# Motor1.net
KiCad netlist of a schematic drawn in Altium Designer
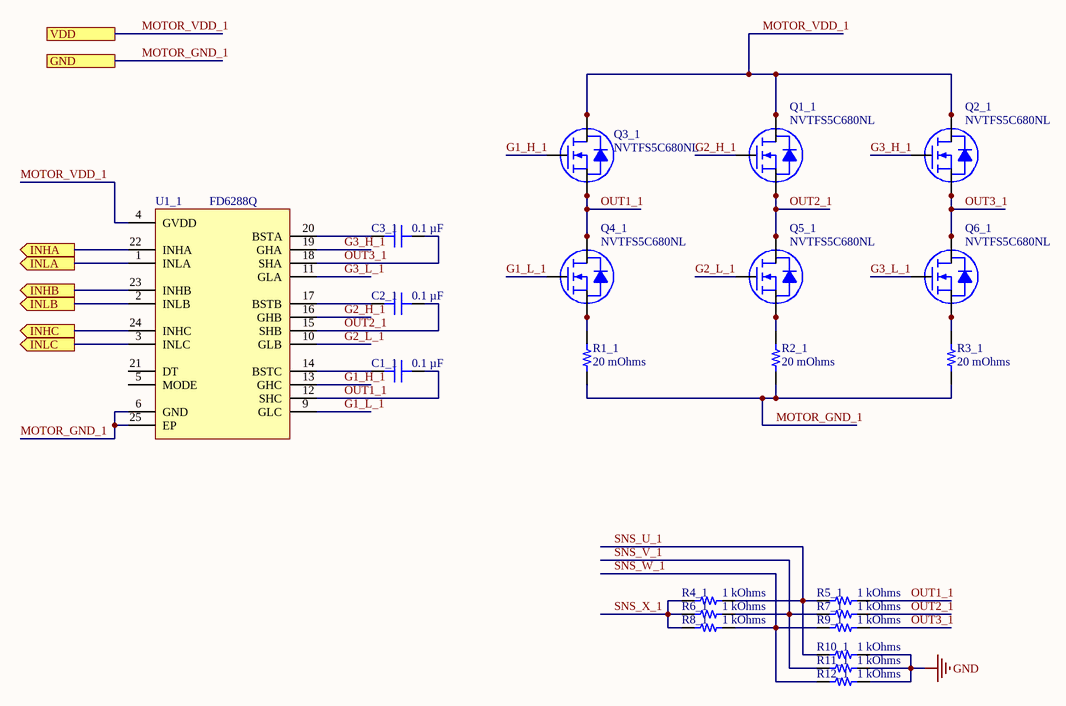
[diagram p0: Motor1.SchDoc]

(export (version "E")
  (design (tool "Eeschema 10.0.6"))
  (components
    (comp (ref "C1_1")
      (value "0.1 µF")
      (footprint "CAP 0402_1005")
      (description "CAP CER 0.1UF 16V X7R 0402")
      (fields (field (name "PART NUMBER") "C0402C104K4RACAUTO") (field (name "MANUFACTURER") "KEMET"))
      (libsource (lib "Celestial Altium Library - altium_library") (part "Capacitor"))
    )
    (comp (ref "C2_1")
      (value "0.1 µF")
      (footprint "CAP 0402_1005")
      (description "CAP CER 0.1UF 16V X7R 0402")
      (fields (field (name "PART NUMBER") "C0402C104K4RACAUTO") (field (name "MANUFACTURER") "KEMET"))
      (libsource (lib "Celestial Altium Library - altium_library") (part "Capacitor"))
    )
    (comp (ref "C3_1")
      (value "0.1 µF")
      (footprint "CAP 0402_1005")
      (description "CAP CER 0.1UF 16V X7R 0402")
      (fields (field (name "PART NUMBER") "C0402C104K4RACAUTO") (field (name "MANUFACTURER") "KEMET"))
      (libsource (lib "Celestial Altium Library - altium_library") (part "Capacitor"))
    )
    (comp (ref "Q1_1")
      (value "NVTFS5C680NL")
      (footprint "NVTFS015N04CTAG")
      (description "N-FET")
      (libsource (lib "IC") (part "NVTFS5C680NL"))
    )
    (comp (ref "Q2_1")
      (value "NVTFS5C680NL")
      (footprint "NVTFS015N04CTAG")
      (description "N-FET")
      (libsource (lib "IC") (part "NVTFS5C680NL"))
    )
    (comp (ref "Q3_1")
      (value "NVTFS5C680NL")
      (footprint "NVTFS015N04CTAG")
      (description "N-FET")
      (libsource (lib "IC") (part "NVTFS5C680NL"))
    )
    (comp (ref "Q4_1")
      (value "NVTFS5C680NL")
      (footprint "NVTFS015N04CTAG")
      (description "N-FET")
      (libsource (lib "IC") (part "NVTFS5C680NL"))
    )
    (comp (ref "Q5_1")
      (value "NVTFS5C680NL")
      (footprint "NVTFS015N04CTAG")
      (description "N-FET")
      (libsource (lib "IC") (part "NVTFS5C680NL"))
    )
    (comp (ref "Q6_1")
      (value "NVTFS5C680NL")
      (footprint "NVTFS015N04CTAG")
      (description "N-FET")
      (libsource (lib "IC") (part "NVTFS5C680NL"))
    )
    (comp (ref "R1_1")
      (value "20 mOhms")
      (footprint "STACKPOLE CSR0805")
      (description "RES 0.02 OHM 1% 1/3W 0603")
      (fields
        (field (name "PART NUMBER") "ERJ-3BWFR020V")
        (field (name "MANUFACTURER") "Panasonic Electronic Components")
      )
      (libsource (lib "Celestial Altium Library - altium_library") (part "Resistor"))
    )
    (comp (ref "R2_1")
      (value "20 mOhms")
      (footprint "STACKPOLE CSR0805")
      (description "RES 0.02 OHM 1% 1/3W 0603")
      (fields
        (field (name "PART NUMBER") "ERJ-3BWFR020V")
        (field (name "MANUFACTURER") "Panasonic Electronic Components")
      )
      (libsource (lib "Celestial Altium Library - altium_library") (part "Resistor"))
    )
    (comp (ref "R3_1")
      (value "20 mOhms")
      (footprint "STACKPOLE CSR0805")
      (description "RES 0.02 OHM 1% 1/3W 0603")
      (fields
        (field (name "PART NUMBER") "ERJ-3BWFR020V")
        (field (name "MANUFACTURER") "Panasonic Electronic Components")
      )
      (libsource (lib "Celestial Altium Library - altium_library") (part "Resistor"))
    )
    (comp (ref "R4_1")
      (value "1 kOhms")
      (footprint "RES 0402_1005")
      (description "RES 14.3K OHM 1% 1/10W 0402")
      (fields
        (field (name "PART NUMBER") "RK73H1ETTP1432F")
        (field (name "MANUFACTURER") "KOA Speer Electronics, Inc.")
      )
      (libsource (lib "Celestial Altium Library - altium_library") (part "Resistor"))
    )
    (comp (ref "R5_1")
      (value "1 kOhms")
      (footprint "RES 0402_1005")
      (description "RES 14.3K OHM 1% 1/10W 0402")
      (fields
        (field (name "PART NUMBER") "RK73H1ETTP1432F")
        (field (name "MANUFACTURER") "KOA Speer Electronics, Inc.")
      )
      (libsource (lib "Celestial Altium Library - altium_library") (part "Resistor"))
    )
    (comp (ref "R6_1")
      (value "1 kOhms")
      (footprint "RES 0402_1005")
      (description "RES 14.3K OHM 1% 1/10W 0402")
      (fields
        (field (name "PART NUMBER") "RK73H1ETTP1432F")
        (field (name "MANUFACTURER") "KOA Speer Electronics, Inc.")
      )
      (libsource (lib "Celestial Altium Library - altium_library") (part "Resistor"))
    )
    (comp (ref "R7_1")
      (value "1 kOhms")
      (footprint "RES 0402_1005")
      (description "RES 14.3K OHM 1% 1/10W 0402")
      (fields
        (field (name "PART NUMBER") "RK73H1ETTP1432F")
        (field (name "MANUFACTURER") "KOA Speer Electronics, Inc.")
      )
      (libsource (lib "Celestial Altium Library - altium_library") (part "Resistor"))
    )
    (comp (ref "R8_1")
      (value "1 kOhms")
      (footprint "RES 0402_1005")
      (description "RES 14.3K OHM 1% 1/10W 0402")
      (fields
        (field (name "PART NUMBER") "RK73H1ETTP1432F")
        (field (name "MANUFACTURER") "KOA Speer Electronics, Inc.")
      )
      (libsource (lib "Celestial Altium Library - altium_library") (part "Resistor"))
    )
    (comp (ref "R9_1")
      (value "1 kOhms")
      (footprint "RES 0402_1005")
      (description "RES 14.3K OHM 1% 1/10W 0402")
      (fields
        (field (name "PART NUMBER") "RK73H1ETTP1432F")
        (field (name "MANUFACTURER") "KOA Speer Electronics, Inc.")
      )
      (libsource (lib "Celestial Altium Library - altium_library") (part "Resistor"))
    )
    (comp (ref "R10_1")
      (value "1 kOhms")
      (footprint "RES 0402_1005")
      (description "RES 14.3K OHM 1% 1/10W 0402")
      (fields
        (field (name "PART NUMBER") "RK73H1ETTP1432F")
        (field (name "MANUFACTURER") "KOA Speer Electronics, Inc.")
      )
      (libsource (lib "Celestial Altium Library - altium_library") (part "Resistor"))
    )
    (comp (ref "R11_1")
      (value "1 kOhms")
      (footprint "RES 0402_1005")
      (description "RES 14.3K OHM 1% 1/10W 0402")
      (fields
        (field (name "PART NUMBER") "RK73H1ETTP1432F")
        (field (name "MANUFACTURER") "KOA Speer Electronics, Inc.")
      )
      (libsource (lib "Celestial Altium Library - altium_library") (part "Resistor"))
    )
    (comp (ref "R12_1")
      (value "1 kOhms")
      (footprint "RES 0402_1005")
      (description "RES 14.3K OHM 1% 1/10W 0402")
      (fields
        (field (name "PART NUMBER") "RK73H1ETTP1432F")
        (field (name "MANUFACTURER") "KOA Speer Electronics, Inc.")
      )
      (libsource (lib "Celestial Altium Library - altium_library") (part "Resistor"))
    )
    (comp (ref "U1_1")
      (value "FD6288Q")
      (footprint "QFN50P400X400X100-25N")
      (description "3 Phase Gate Driver 1.5-2.2A")
      (fields (field (name "MF") "Texas Instruments") (field (name "MP") "UCC27282DRCR"))
      (libsource (lib "IC") (part "FD6288Q"))
    )
  )
  (nets
    (net (code "1") (name "/G1_H_1") (class "Default")
      (node (ref "Q3_1") (pin "4") (pinfunction "G_4") (pintype "passive"))
      (node (ref "U1_1") (pin "13") (pinfunction "GHC_13") (pintype "passive"))
    )
    (net (code "2") (name "/G1_L_1") (class "Default")
      (node (ref "Q4_1") (pin "4") (pinfunction "G_4") (pintype "passive"))
      (node (ref "U1_1") (pin "9") (pinfunction "GLC_9") (pintype "passive"))
    )
    (net (code "3") (name "/G2_H_1") (class "Default")
      (node (ref "Q1_1") (pin "4") (pinfunction "G_4") (pintype "passive"))
      (node (ref "U1_1") (pin "16") (pinfunction "GHB_16") (pintype "passive"))
    )
    (net (code "4") (name "/G2_L_1") (class "Default")
      (node (ref "Q5_1") (pin "4") (pinfunction "G_4") (pintype "passive"))
      (node (ref "U1_1") (pin "10") (pinfunction "GLB_10") (pintype "passive"))
    )
    (net (code "5") (name "/G3_H_1") (class "Default")
      (node (ref "Q2_1") (pin "4") (pinfunction "G_4") (pintype "passive"))
      (node (ref "U1_1") (pin "19") (pinfunction "GHA_19") (pintype "passive"))
    )
    (net (code "6") (name "/G3_L_1") (class "Default")
      (node (ref "Q6_1") (pin "4") (pinfunction "G_4") (pintype "passive"))
      (node (ref "U1_1") (pin "11") (pinfunction "GLA_11") (pintype "passive"))
    )
    (net (code "7") (name "/INHA") (class "Default")
      (node (ref "U1_1") (pin "22") (pinfunction "INHA_22") (pintype "passive"))
    )
    (net (code "8") (name "/INHB") (class "Default")
      (node (ref "U1_1") (pin "23") (pinfunction "INHB_23") (pintype "passive"))
    )
    (net (code "9") (name "/INHC") (class "Default")
      (node (ref "U1_1") (pin "24") (pinfunction "INHC_24") (pintype "passive"))
    )
    (net (code "10") (name "/INLA") (class "Default")
      (node (ref "U1_1") (pin "1") (pinfunction "INLA_1") (pintype "passive"))
    )
    (net (code "11") (name "/INLB") (class "Default")
      (node (ref "U1_1") (pin "2") (pinfunction "INLB_2") (pintype "passive"))
    )
    (net (code "12") (name "/INLC") (class "Default")
      (node (ref "U1_1") (pin "3") (pinfunction "INLC_3") (pintype "passive"))
    )
    (net (code "13") (name "/MOTOR_VDD_1") (class "Default")
      (node (ref "Q1_1") (pin "5") (pinfunction "D_5") (pintype "passive"))
      (node (ref "Q1_1") (pin "6") (pinfunction "D_6") (pintype "passive"))
      (node (ref "Q1_1") (pin "7") (pinfunction "D_7") (pintype "passive"))
      (node (ref "Q1_1") (pin "8") (pinfunction "D_8") (pintype "passive"))
      (node (ref "Q2_1") (pin "5") (pinfunction "D_5") (pintype "passive"))
      (node (ref "Q2_1") (pin "6") (pinfunction "D_6") (pintype "passive"))
      (node (ref "Q2_1") (pin "7") (pinfunction "D_7") (pintype "passive"))
      (node (ref "Q2_1") (pin "8") (pinfunction "D_8") (pintype "passive"))
      (node (ref "Q3_1") (pin "5") (pinfunction "D_5") (pintype "passive"))
      (node (ref "Q3_1") (pin "6") (pinfunction "D_6") (pintype "passive"))
      (node (ref "Q3_1") (pin "7") (pinfunction "D_7") (pintype "passive"))
      (node (ref "Q3_1") (pin "8") (pinfunction "D_8") (pintype "passive"))
      (node (ref "U1_1") (pin "4") (pinfunction "GVDD_4") (pintype "passive"))
    )
    (net (code "14") (name "/OUT1_1") (class "Default")
      (node (ref "C1_1") (pin "2") (pinfunction "2_2") (pintype "passive"))
      (node (ref "Q3_1") (pin "1") (pinfunction "S_1") (pintype "passive"))
      (node (ref "Q3_1") (pin "2") (pinfunction "S_2") (pintype "passive"))
      (node (ref "Q3_1") (pin "3") (pinfunction "S_3") (pintype "passive"))
      (node (ref "Q4_1") (pin "5") (pinfunction "D_5") (pintype "passive"))
      (node (ref "Q4_1") (pin "6") (pinfunction "D_6") (pintype "passive"))
      (node (ref "Q4_1") (pin "7") (pinfunction "D_7") (pintype "passive"))
      (node (ref "Q4_1") (pin "8") (pinfunction "D_8") (pintype "passive"))
      (node (ref "R5_1") (pin "2") (pinfunction "2_2") (pintype "passive"))
      (node (ref "U1_1") (pin "12") (pinfunction "SHC_12") (pintype "passive"))
    )
    (net (code "15") (name "/OUT2_1") (class "Default")
      (node (ref "C2_1") (pin "2") (pinfunction "2_2") (pintype "passive"))
      (node (ref "Q1_1") (pin "1") (pinfunction "S_1") (pintype "passive"))
      (node (ref "Q1_1") (pin "2") (pinfunction "S_2") (pintype "passive"))
      (node (ref "Q1_1") (pin "3") (pinfunction "S_3") (pintype "passive"))
      (node (ref "Q5_1") (pin "5") (pinfunction "D_5") (pintype "passive"))
      (node (ref "Q5_1") (pin "6") (pinfunction "D_6") (pintype "passive"))
      (node (ref "Q5_1") (pin "7") (pinfunction "D_7") (pintype "passive"))
      (node (ref "Q5_1") (pin "8") (pinfunction "D_8") (pintype "passive"))
      (node (ref "R7_1") (pin "2") (pinfunction "2_2") (pintype "passive"))
      (node (ref "U1_1") (pin "15") (pinfunction "SHB_15") (pintype "passive"))
    )
    (net (code "16") (name "/OUT3_1") (class "Default")
      (node (ref "C3_1") (pin "2") (pinfunction "2_2") (pintype "passive"))
      (node (ref "Q2_1") (pin "1") (pinfunction "S_1") (pintype "passive"))
      (node (ref "Q2_1") (pin "2") (pinfunction "S_2") (pintype "passive"))
      (node (ref "Q2_1") (pin "3") (pinfunction "S_3") (pintype "passive"))
      (node (ref "Q6_1") (pin "5") (pinfunction "D_5") (pintype "passive"))
      (node (ref "Q6_1") (pin "6") (pinfunction "D_6") (pintype "passive"))
      (node (ref "Q6_1") (pin "7") (pinfunction "D_7") (pintype "passive"))
      (node (ref "Q6_1") (pin "8") (pinfunction "D_8") (pintype "passive"))
      (node (ref "R9_1") (pin "2") (pinfunction "2_2") (pintype "passive"))
      (node (ref "U1_1") (pin "18") (pinfunction "SHA_18") (pintype "passive"))
    )
    (net (code "17") (name "/SNS_U_1") (class "Default")
      (node (ref "R10_1") (pin "2") (pinfunction "2_2") (pintype "passive"))
      (node (ref "R4_1") (pin "2") (pinfunction "2_2") (pintype "passive"))
      (node (ref "R5_1") (pin "1") (pinfunction "1_1") (pintype "passive"))
    )
    (net (code "18") (name "/SNS_V_1") (class "Default")
      (node (ref "R11_1") (pin "2") (pinfunction "2_2") (pintype "passive"))
      (node (ref "R6_1") (pin "2") (pinfunction "2_2") (pintype "passive"))
      (node (ref "R7_1") (pin "1") (pinfunction "1_1") (pintype "passive"))
    )
    (net (code "19") (name "/SNS_W_1") (class "Default")
      (node (ref "R12_1") (pin "2") (pinfunction "2_2") (pintype "passive"))
      (node (ref "R8_1") (pin "2") (pinfunction "2_2") (pintype "passive"))
      (node (ref "R9_1") (pin "1") (pinfunction "1_1") (pintype "passive"))
    )
    (net (code "20") (name "/SNS_X_1") (class "Default")
      (node (ref "R4_1") (pin "1") (pinfunction "1_1") (pintype "passive"))
      (node (ref "R6_1") (pin "1") (pinfunction "1_1") (pintype "passive"))
      (node (ref "R8_1") (pin "1") (pinfunction "1_1") (pintype "passive"))
    )
    (net (code "21") (name "GND") (class "Default")
      (node (ref "R10_1") (pin "1") (pinfunction "1_1") (pintype "passive"))
      (node (ref "R11_1") (pin "1") (pinfunction "1_1") (pintype "passive"))
      (node (ref "R12_1") (pin "1") (pinfunction "1_1") (pintype "passive"))
      (node (ref "R1_1") (pin "1") (pinfunction "1_1") (pintype "passive"))
      (node (ref "R2_1") (pin "1") (pinfunction "1_1") (pintype "passive"))
      (node (ref "R3_1") (pin "1") (pinfunction "1_1") (pintype "passive"))
      (node (ref "U1_1") (pin "25") (pinfunction "EP_25") (pintype "passive"))
      (node (ref "U1_1") (pin "6") (pinfunction "GND_6") (pintype "passive"))
    )
    (net (code "22") (name "Net-(Q4_1-S-Pad1)") (class "Default")
      (node (ref "Q4_1") (pin "1") (pinfunction "S_1") (pintype "passive"))
      (node (ref "Q4_1") (pin "2") (pinfunction "S_2") (pintype "passive"))
      (node (ref "Q4_1") (pin "3") (pinfunction "S_3") (pintype "passive"))
      (node (ref "R1_1") (pin "2") (pinfunction "2_2") (pintype "passive"))
    )
    (net (code "23") (name "Net-(Q5_1-S-Pad1)") (class "Default")
      (node (ref "Q5_1") (pin "1") (pinfunction "S_1") (pintype "passive"))
      (node (ref "Q5_1") (pin "2") (pinfunction "S_2") (pintype "passive"))
      (node (ref "Q5_1") (pin "3") (pinfunction "S_3") (pintype "passive"))
      (node (ref "R2_1") (pin "2") (pinfunction "2_2") (pintype "passive"))
    )
    (net (code "24") (name "Net-(Q6_1-S-Pad1)") (class "Default")
      (node (ref "Q6_1") (pin "1") (pinfunction "S_1") (pintype "passive"))
      (node (ref "Q6_1") (pin "2") (pinfunction "S_2") (pintype "passive"))
      (node (ref "Q6_1") (pin "3") (pinfunction "S_3") (pintype "passive"))
      (node (ref "R3_1") (pin "2") (pinfunction "2_2") (pintype "passive"))
    )
    (net (code "25") (name "Net-(U1_1-BSTA)") (class "Default")
      (node (ref "C3_1") (pin "1") (pinfunction "1_1") (pintype "passive"))
      (node (ref "U1_1") (pin "20") (pinfunction "BSTA_20") (pintype "passive"))
    )
    (net (code "26") (name "Net-(U1_1-BSTB)") (class "Default")
      (node (ref "C2_1") (pin "1") (pinfunction "1_1") (pintype "passive"))
      (node (ref "U1_1") (pin "17") (pinfunction "BSTB_17") (pintype "passive"))
    )
    (net (code "27") (name "Net-(U1_1-BSTC)") (class "Default")
      (node (ref "C1_1") (pin "1") (pinfunction "1_1") (pintype "passive"))
      (node (ref "U1_1") (pin "14") (pinfunction "BSTC_14") (pintype "passive"))
    )
    (net (code "28") (name "unconnected-(U1_1-DT-Pad21)") (class "Default")
      (node (ref "U1_1") (pin "21") (pinfunction "DT_21") (pintype "passive"))
    )
    (net (code "29") (name "unconnected-(U1_1-MODE-Pad5)") (class "Default")
      (node (ref "U1_1") (pin "5") (pinfunction "MODE_5") (pintype "passive"))
    )
  )
)
